# esp8266.net
KiCad netlist of a schematic drawn in EAGLE
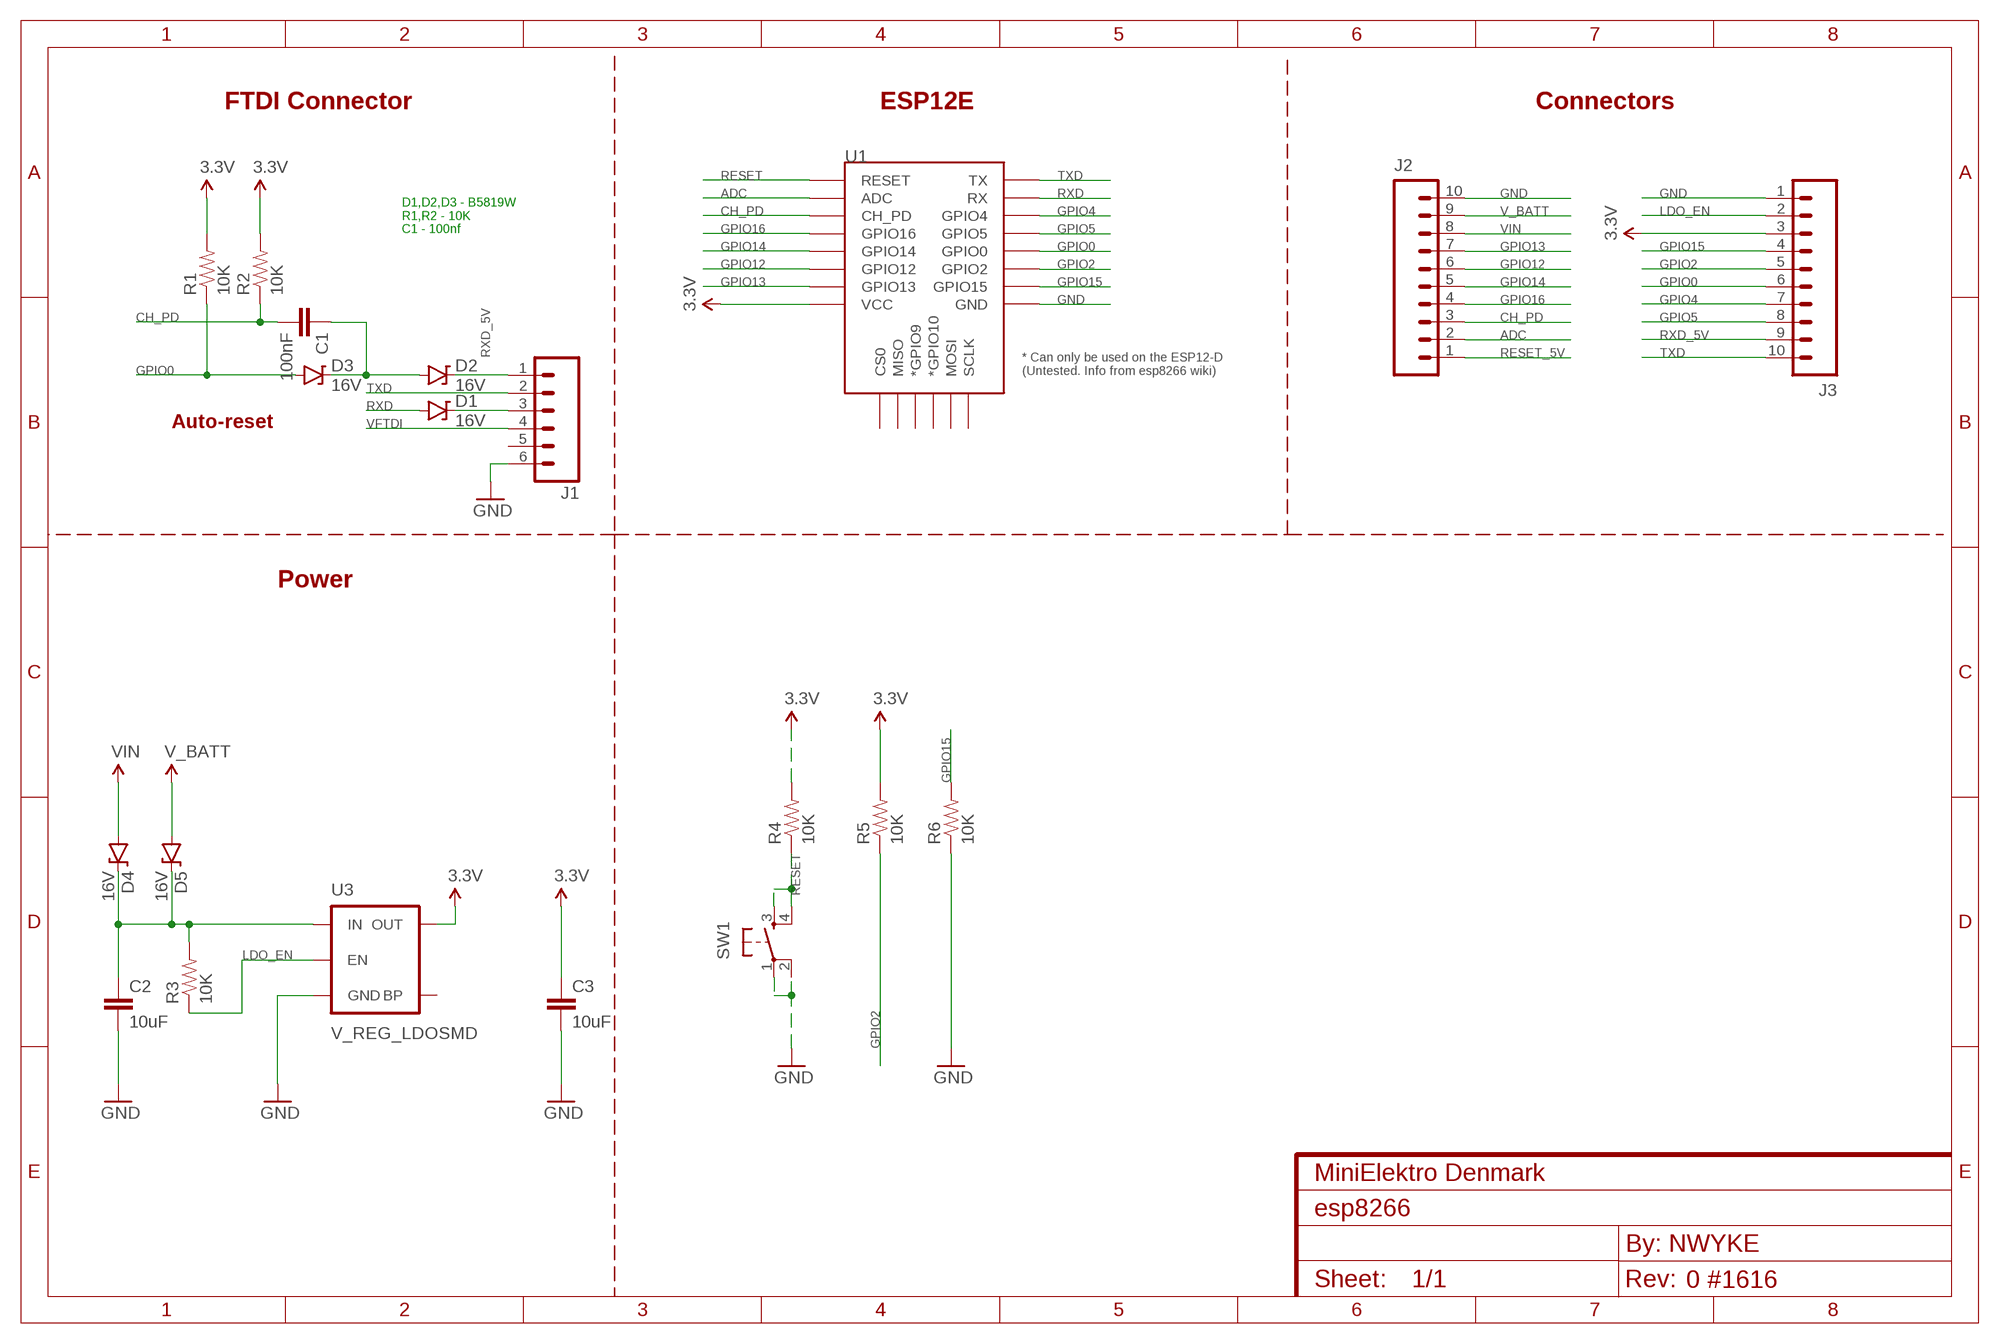
[diagram p0: schematic, sheet 1]

(export (version "E")
  (design (tool "Eeschema 10.0.6"))
  (components
    (comp (ref "C1")
      (value "100nF")
      (footprint "eagle-import:0402-CAP")
      (libsource (lib "eagle-import") (part "CAP0402-CAP"))
    )
    (comp (ref "C2")
      (value "10uF")
      (footprint "eagle-import:0402-CAP")
      (libsource (lib "eagle-import") (part "CAP0402-CAP"))
    )
    (comp (ref "C3")
      (value "10uF")
      (footprint "eagle-import:0402-CAP")
      (libsource (lib "eagle-import") (part "CAP0402-CAP"))
    )
    (comp (ref "D1")
      (value "16V")
      (footprint "eagle-import:SOD-123")
      (libsource (lib "eagle-import") (part "DIODE-ZENER16V"))
    )
    (comp (ref "D2")
      (value "16V")
      (footprint "eagle-import:SOD-123")
      (libsource (lib "eagle-import") (part "DIODE-ZENER16V"))
    )
    (comp (ref "D3")
      (value "16V")
      (footprint "eagle-import:SOD-123")
      (libsource (lib "eagle-import") (part "DIODE-ZENER16V"))
    )
    (comp (ref "D4")
      (value "16V")
      (footprint "eagle-import:SOD-123")
      (libsource (lib "eagle-import") (part "DIODE-ZENER16V"))
    )
    (comp (ref "D5")
      (value "16V")
      (footprint "eagle-import:SOD-123")
      (libsource (lib "eagle-import") (part "DIODE-ZENER16V"))
    )
    (comp (ref "J1")
      (value "M06SILK_FEMALE_PTH")
      (footprint "eagle-import:1X06")
      (libsource (lib "eagle-import") (part "M06SILK_FEMALE_PTH"))
    )
    (comp (ref "J2")
      (value "M10SILK_FEMALE_PTH")
      (footprint "eagle-import:1X10")
      (libsource (lib "eagle-import") (part "M10SILK_FEMALE_PTH"))
    )
    (comp (ref "J3")
      (value "M10SILK_FEMALE_PTH")
      (footprint "eagle-import:1X10")
      (libsource (lib "eagle-import") (part "M10SILK_FEMALE_PTH"))
    )
    (comp (ref "R1")
      (value "10K")
      (footprint "eagle-import:0402-RES")
      (libsource (lib "eagle-import") (part "RESISTOR0402-RES"))
    )
    (comp (ref "R2")
      (value "10K")
      (footprint "eagle-import:0402-RES")
      (libsource (lib "eagle-import") (part "RESISTOR0402-RES"))
    )
    (comp (ref "R3")
      (value "10K")
      (footprint "eagle-import:0402-RES")
      (libsource (lib "eagle-import") (part "RESISTOR0402-RES"))
    )
    (comp (ref "R4")
      (value "10K")
      (footprint "eagle-import:0402-RES")
      (libsource (lib "eagle-import") (part "RESISTOR0402-RES"))
    )
    (comp (ref "R5")
      (value "10K")
      (footprint "eagle-import:0402-RES")
      (libsource (lib "eagle-import") (part "RESISTOR0402-RES"))
    )
    (comp (ref "R6")
      (value "10K")
      (footprint "eagle-import:0402-RES")
      (libsource (lib "eagle-import") (part "RESISTOR0402-RES"))
    )
    (comp (ref "SW1")
      (value "SWITCH_SPST_4_PINRECT")
      (footprint "eagle-import:TACTILE_SWITCH_SMD_4.6X2.8MM")
      (libsource (lib "eagle-import") (part "SWITCH_SPST_4_PINRECT"))
    )
    (comp (ref "U1")
      (value "ESP12ESMD")
      (footprint "eagle-import:ESP12E-SMD")
      (libsource (lib "eagle-import") (part "ESP12ESMD"))
    )
    (comp (ref "U3")
      (value "V_REG_LDOSMD")
      (footprint "eagle-import:SOT23-5")
      (libsource (lib "eagle-import") (part "V_REG_LDOSMD"))
    )
  )
  (nets
    (net (code "1") (name "/ADC") (class "Default")
      (node (ref "J2") (pin "2") (pinfunction "2_2") (pintype "passive"))
      (node (ref "U1") (pin "ADC") (pinfunction "ADC_ADC") (pintype "bidirectional"))
    )
    (net (code "2") (name "/CH_PD") (class "Default")
      (node (ref "C1") (pin "2") (pinfunction "2_2") (pintype "passive"))
      (node (ref "J2") (pin "3") (pinfunction "3_3") (pintype "passive"))
      (node (ref "R2") (pin "1") (pinfunction "1_1") (pintype "passive"))
      (node (ref "U1") (pin "CH_PD") (pinfunction "CH_PD_CH_PD") (pintype "bidirectional"))
    )
    (net (code "3") (name "/GPIO0") (class "Default")
      (node (ref "D3") (pin "A") (pinfunction "A_A") (pintype "passive"))
      (node (ref "J3") (pin "6") (pinfunction "6_6") (pintype "passive"))
      (node (ref "R1") (pin "1") (pinfunction "1_1") (pintype "passive"))
      (node (ref "U1") (pin "GPIO0") (pinfunction "GPIO0_GPIO0") (pintype "bidirectional"))
    )
    (net (code "4") (name "/GPIO2") (class "Default")
      (node (ref "J3") (pin "5") (pinfunction "5_5") (pintype "passive"))
      (node (ref "R5") (pin "1") (pinfunction "1_1") (pintype "passive"))
      (node (ref "U1") (pin "GPIO2") (pinfunction "GPIO2_GPIO2") (pintype "bidirectional"))
    )
    (net (code "5") (name "/GPIO4") (class "Default")
      (node (ref "J3") (pin "7") (pinfunction "7_7") (pintype "passive"))
      (node (ref "U1") (pin "GPIO4") (pinfunction "GPIO4_GPIO4") (pintype "bidirectional"))
    )
    (net (code "6") (name "/GPIO5") (class "Default")
      (node (ref "J3") (pin "8") (pinfunction "8_8") (pintype "passive"))
      (node (ref "U1") (pin "GPIO5") (pinfunction "GPIO5_GPIO5") (pintype "bidirectional"))
    )
    (net (code "7") (name "/GPIO12") (class "Default")
      (node (ref "J2") (pin "6") (pinfunction "6_6") (pintype "passive"))
      (node (ref "U1") (pin "GPIO12") (pinfunction "GPIO12_GPIO12") (pintype "bidirectional"))
    )
    (net (code "8") (name "/GPIO13") (class "Default")
      (node (ref "J2") (pin "7") (pinfunction "7_7") (pintype "passive"))
      (node (ref "U1") (pin "GPIO13") (pinfunction "GPIO13_GPIO13") (pintype "bidirectional"))
    )
    (net (code "9") (name "/GPIO14") (class "Default")
      (node (ref "J2") (pin "5") (pinfunction "5_5") (pintype "passive"))
      (node (ref "U1") (pin "GPIO14") (pinfunction "GPIO14_GPIO14") (pintype "bidirectional"))
    )
    (net (code "10") (name "/GPIO15") (class "Default")
      (node (ref "J3") (pin "4") (pinfunction "4_4") (pintype "passive"))
      (node (ref "R6") (pin "2") (pinfunction "2_2") (pintype "passive"))
      (node (ref "U1") (pin "GPIO15") (pinfunction "GPIO15_GPIO15") (pintype "bidirectional"))
    )
    (net (code "11") (name "/GPIO16") (class "Default")
      (node (ref "J2") (pin "4") (pinfunction "4_4") (pintype "passive"))
      (node (ref "U1") (pin "GPIO16") (pinfunction "GPIO16_GPIO16") (pintype "bidirectional"))
    )
    (net (code "12") (name "/LDO_EN") (class "Default")
      (node (ref "J3") (pin "2") (pinfunction "2_2") (pintype "passive"))
      (node (ref "R3") (pin "1") (pinfunction "1_1") (pintype "passive"))
      (node (ref "U3") (pin "3") (pinfunction "EN_3") (pintype "input"))
    )
    (net (code "13") (name "/RESET") (class "Default")
      (node (ref "R4") (pin "1") (pinfunction "1_1") (pintype "passive"))
      (node (ref "SW1") (pin "3") (pinfunction "3_3") (pintype "passive"))
      (node (ref "SW1") (pin "4") (pinfunction "4_4") (pintype "passive"))
      (node (ref "U1") (pin "RESET") (pinfunction "RESET_RESET") (pintype "bidirectional"))
    )
    (net (code "14") (name "/RESET_5V") (class "Default")
      (node (ref "J2") (pin "1") (pinfunction "1_1") (pintype "passive"))
    )
    (net (code "15") (name "/RXD") (class "Default")
      (node (ref "D1") (pin "A") (pinfunction "A_A") (pintype "passive"))
      (node (ref "U1") (pin "RXD0") (pinfunction "RX_RXD0") (pintype "bidirectional"))
    )
    (net (code "16") (name "/RXD_5V") (class "Default")
      (node (ref "D1") (pin "C") (pinfunction "C_C") (pintype "passive"))
      (node (ref "J1") (pin "3") (pinfunction "3_3") (pintype "passive"))
      (node (ref "J3") (pin "9") (pinfunction "9_9") (pintype "passive"))
    )
    (net (code "17") (name "/TXD") (class "Default")
      (node (ref "J1") (pin "2") (pinfunction "2_2") (pintype "passive"))
      (node (ref "J3") (pin "10") (pinfunction "10_10") (pintype "passive"))
      (node (ref "U1") (pin "TXD0") (pinfunction "TX_TXD0") (pintype "bidirectional"))
    )
    (net (code "18") (name "/VFTDI") (class "Default")
      (node (ref "J1") (pin "4") (pinfunction "4_4") (pintype "passive"))
    )
    (net (code "19") (name "3.3V") (class "Default")
      (node (ref "C3") (pin "1") (pinfunction "1_1") (pintype "passive"))
      (node (ref "J3") (pin "3") (pinfunction "3_3") (pintype "passive"))
      (node (ref "R1") (pin "2") (pinfunction "2_2") (pintype "passive"))
      (node (ref "R2") (pin "2") (pinfunction "2_2") (pintype "passive"))
      (node (ref "R4") (pin "2") (pinfunction "2_2") (pintype "passive"))
      (node (ref "R5") (pin "2") (pinfunction "2_2") (pintype "passive"))
      (node (ref "U1") (pin "VCC") (pinfunction "VCC_VCC") (pintype "bidirectional"))
      (node (ref "U3") (pin "5") (pinfunction "OUT_5") (pintype "passive"))
    )
    (net (code "20") (name "GND") (class "Default")
      (node (ref "C2") (pin "2") (pinfunction "2_2") (pintype "passive"))
      (node (ref "C3") (pin "2") (pinfunction "2_2") (pintype "passive"))
      (node (ref "J1") (pin "6") (pinfunction "6_6") (pintype "passive"))
      (node (ref "J2") (pin "10") (pinfunction "10_10") (pintype "passive"))
      (node (ref "J3") (pin "1") (pinfunction "1_1") (pintype "passive"))
      (node (ref "R6") (pin "1") (pinfunction "1_1") (pintype "passive"))
      (node (ref "SW1") (pin "1") (pinfunction "1_1") (pintype "passive"))
      (node (ref "SW1") (pin "2") (pinfunction "2_2") (pintype "passive"))
      (node (ref "U1") (pin "GND") (pinfunction "GND_GND") (pintype "bidirectional"))
      (node (ref "U3") (pin "2") (pinfunction "GND_2") (pintype "input"))
    )
    (net (code "21") (name "Net-(C1-Pad1)") (class "Default")
      (node (ref "C1") (pin "1") (pinfunction "1_1") (pintype "passive"))
      (node (ref "D2") (pin "A") (pinfunction "A_A") (pintype "passive"))
      (node (ref "D3") (pin "C") (pinfunction "C_C") (pintype "passive"))
    )
    (net (code "22") (name "Net-(D2-PadC)") (class "Default")
      (node (ref "D2") (pin "C") (pinfunction "C_C") (pintype "passive"))
      (node (ref "J1") (pin "1") (pinfunction "1_1") (pintype "passive"))
    )
    (net (code "23") (name "Net-(U3-IN)") (class "Default")
      (node (ref "C2") (pin "1") (pinfunction "1_1") (pintype "passive"))
      (node (ref "D4") (pin "C") (pinfunction "C_C") (pintype "passive"))
      (node (ref "D5") (pin "C") (pinfunction "C_C") (pintype "passive"))
      (node (ref "R3") (pin "2") (pinfunction "2_2") (pintype "passive"))
      (node (ref "U3") (pin "1") (pinfunction "IN_1") (pintype "input"))
    )
    (net (code "24") (name "VIN") (class "Default")
      (node (ref "D4") (pin "A") (pinfunction "A_A") (pintype "passive"))
      (node (ref "J2") (pin "8") (pinfunction "8_8") (pintype "passive"))
    )
    (net (code "25") (name "V_BATT") (class "Default")
      (node (ref "D5") (pin "A") (pinfunction "A_A") (pintype "passive"))
      (node (ref "J2") (pin "9") (pinfunction "9_9") (pintype "passive"))
    )
    (net (code "26") (name "unconnected-(J1-Pad5)") (class "Default")
      (node (ref "J1") (pin "5") (pinfunction "5_5") (pintype "passive"))
    )
    (net (code "27") (name "unconnected-(U1-*GPIO9-PadGPIO9)") (class "Default")
      (node (ref "U1") (pin "GPIO9") (pinfunction "*GPIO9_GPIO9") (pintype "bidirectional"))
    )
    (net (code "28") (name "unconnected-(U1-*GPIO10-PadGPIO10)") (class "Default")
      (node (ref "U1") (pin "GPIO10") (pinfunction "*GPIO10_GPIO10") (pintype "bidirectional"))
    )
    (net (code "29") (name "unconnected-(U1-PadCS0)") (class "Default")
      (node (ref "U1") (pin "CS0") (pinfunction "CS0_CS0") (pintype "bidirectional"))
    )
    (net (code "30") (name "unconnected-(U1-PadMISO)") (class "Default")
      (node (ref "U1") (pin "MISO") (pinfunction "MISO_MISO") (pintype "bidirectional"))
    )
    (net (code "31") (name "unconnected-(U1-PadMOSI)") (class "Default")
      (node (ref "U1") (pin "MOSI") (pinfunction "MOSI_MOSI") (pintype "bidirectional"))
    )
    (net (code "32") (name "unconnected-(U1-PadSCLK)") (class "Default")
      (node (ref "U1") (pin "SCLK") (pinfunction "SCLK_SCLK") (pintype "bidirectional"))
    )
    (net (code "33") (name "unconnected-(U3-BP-Pad4)") (class "Default")
      (node (ref "U3") (pin "4") (pinfunction "BP_4") (pintype "input"))
    )
  )
)
